# ReflowMaster.net
KiCad netlist of a schematic drawn in EAGLE
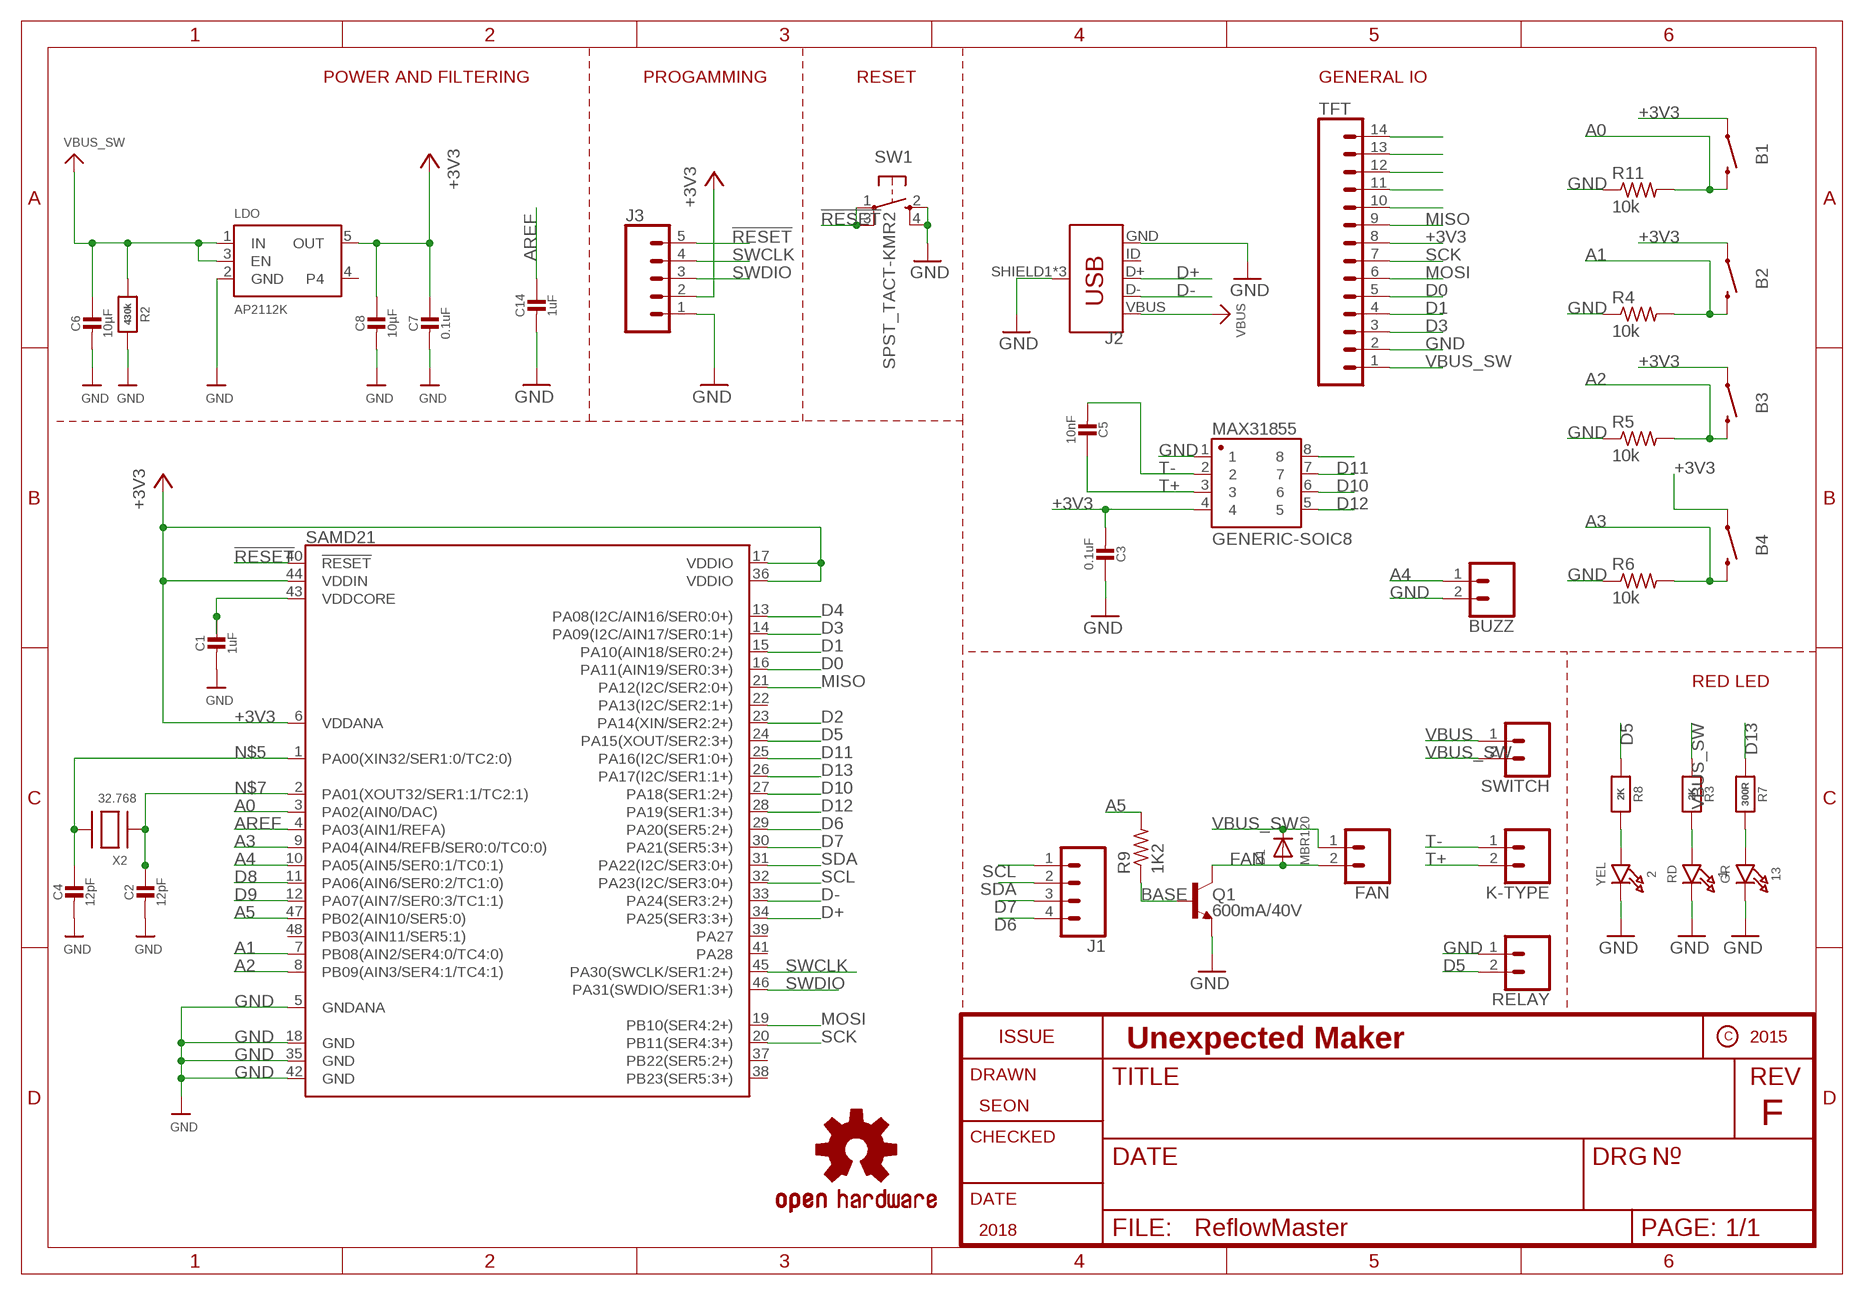
[diagram p0: schematic, sheet 1]

(export (version "E")
  (design (tool "Eeschema 10.0.6"))
  (components
    (comp (ref "1")
      (value "RD")
      (footprint "eagle-import:CHIPLED_0805_NOOUTLINE")
      (libsource (lib "eagle-import") (part "LED0805_NOOUTLINE"))
    )
    (comp (ref "2")
      (value "YEL")
      (footprint "eagle-import:CHIPLED_0805_NOOUTLINE")
      (libsource (lib "eagle-import") (part "LED0805_NOOUTLINE"))
    )
    (comp (ref "13")
      (value "GR")
      (footprint "eagle-import:CHIPLED_0805_NOOUTLINE")
      (libsource (lib "eagle-import") (part "LED0805_NOOUTLINE"))
    )
    (comp (ref "B1")
      (value "MOMENTARY-SWITCH-SPST-PTH-RIGHT-ANGLE-KIT")
      (footprint "eagle-import:TACTILE_SWITCH_PTH_RIGHT_ANGLE_KIT")
      (libsource (lib "eagle-import") (part "MOMENTARY-SWITCH-SPST-PTH-RIGHT-ANGLE-KIT"))
    )
    (comp (ref "B2")
      (value "MOMENTARY-SWITCH-SPST-PTH-RIGHT-ANGLE-KIT")
      (footprint "eagle-import:TACTILE_SWITCH_PTH_RIGHT_ANGLE_KIT")
      (libsource (lib "eagle-import") (part "MOMENTARY-SWITCH-SPST-PTH-RIGHT-ANGLE-KIT"))
    )
    (comp (ref "B3")
      (value "MOMENTARY-SWITCH-SPST-PTH-RIGHT-ANGLE-KIT")
      (footprint "eagle-import:TACTILE_SWITCH_PTH_RIGHT_ANGLE_KIT")
      (libsource (lib "eagle-import") (part "MOMENTARY-SWITCH-SPST-PTH-RIGHT-ANGLE-KIT"))
    )
    (comp (ref "B4")
      (value "MOMENTARY-SWITCH-SPST-PTH-RIGHT-ANGLE-KIT")
      (footprint "eagle-import:TACTILE_SWITCH_PTH_RIGHT_ANGLE_KIT")
      (libsource (lib "eagle-import") (part "MOMENTARY-SWITCH-SPST-PTH-RIGHT-ANGLE-KIT"))
    )
    (comp (ref "BUZZ")
      (value "CONN_02")
      (footprint "eagle-import:1X02")
      (libsource (lib "eagle-import") (part "CONN_02"))
    )
    (comp (ref "C1")
      (value "1uF")
      (footprint "eagle-import:0805-NO")
      (libsource (lib "eagle-import") (part "CAP_CERAMIC0805-NOOUTLINE"))
    )
    (comp (ref "C2")
      (value "12pF")
      (footprint "eagle-import:0805-NO")
      (libsource (lib "eagle-import") (part "CAP_CERAMIC0805-NOOUTLINE"))
    )
    (comp (ref "C3")
      (value "0.1uF")
      (footprint "eagle-import:0805-NO")
      (libsource (lib "eagle-import") (part "CAP_CERAMIC0805-NOOUTLINE"))
    )
    (comp (ref "C4")
      (value "12pF")
      (footprint "eagle-import:0805-NO")
      (libsource (lib "eagle-import") (part "CAP_CERAMIC0805-NOOUTLINE"))
    )
    (comp (ref "C5")
      (value "10nF")
      (footprint "eagle-import:0805-NO")
      (libsource (lib "eagle-import") (part "CAP_CERAMIC0805-NOOUTLINE"))
    )
    (comp (ref "C6")
      (value "10µF")
      (footprint "eagle-import:0805-NO")
      (libsource (lib "eagle-import") (part "CAP_CERAMIC0805-NOOUTLINE"))
    )
    (comp (ref "C7")
      (value "0.1uF")
      (footprint "eagle-import:0805-NO")
      (libsource (lib "eagle-import") (part "CAP_CERAMIC0805-NOOUTLINE"))
    )
    (comp (ref "C8")
      (value "10µF")
      (footprint "eagle-import:0805-NO")
      (libsource (lib "eagle-import") (part "CAP_CERAMIC0805-NOOUTLINE"))
    )
    (comp (ref "C14")
      (value "1uF")
      (footprint "eagle-import:0805-NO")
      (libsource (lib "eagle-import") (part "CAP_CERAMIC0805-NOOUTLINE"))
    )
    (comp (ref "D1")
      (value "MBR120")
      (footprint "eagle-import:SOD-123")
      (libsource (lib "eagle-import") (part "DIODESOD-123"))
    )
    (comp (ref "FAN")
      (value "CONN_02")
      (footprint "eagle-import:1X02")
      (libsource (lib "eagle-import") (part "CONN_02"))
    )
    (comp (ref "J1")
      (value "CONN_041X04_NO_SILK")
      (footprint "eagle-import:1X04_NO_SILK")
      (libsource (lib "eagle-import") (part "CONN_041X04_NO_SILK"))
    )
    (comp (ref "J2")
      (value "USB_MICRO-B_FEMALE-SMT")
      (footprint "eagle-import:USB-B-MICRO-SMD")
      (libsource (lib "eagle-import") (part "USB_MICRO-B_FEMALE-SMT"))
    )
    (comp (ref "J3")
      (value "CONN_05NO_SILK")
      (footprint "eagle-import:1X05_NO_SILK")
      (libsource (lib "eagle-import") (part "CONN_05NO_SILK"))
    )
    (comp (ref "K-TYPE")
      (value "CONN_02")
      (footprint "eagle-import:1X02")
      (libsource (lib "eagle-import") (part "CONN_02"))
    )
    (comp (ref "LDO")
      (value "AP2112K")
      (footprint "eagle-import:SOT23-5")
      (libsource (lib "eagle-import") (part "VREG_SOT23-5"))
    )
    (comp (ref "LOGO1")
      (value "OSHW-LOGOS")
      (footprint "eagle-import:OSHW-LOGO-S")
      (libsource (lib "eagle-import") (part "OSHW-LOGOS"))
    )
    (comp (ref "MAX31855")
      (value "GENERIC-SOIC8")
      (footprint "eagle-import:SO08-UNIVERSAL")
      (libsource (lib "eagle-import") (part "GENERIC-SOIC8"))
    )
    (comp (ref "Q1")
      (value "600mA/40V")
      (footprint "eagle-import:SOT23-3")
      (libsource (lib "eagle-import") (part "TRANS_NPN-MMBT2222AL"))
    )
    (comp (ref "R2")
      (value "430k")
      (footprint "eagle-import:0805-NO")
      (libsource (lib "eagle-import") (part "RESISTOR0805_NOOUTLINE"))
    )
    (comp (ref "R3")
      (value "2K")
      (footprint "eagle-import:0805-NO")
      (libsource (lib "eagle-import") (part "RESISTOR0805_NOOUTLINE"))
    )
    (comp (ref "R4")
      (value "10k")
      (footprint "eagle-import:R0805")
      (libsource (lib "eagle-import") (part "R-US_R0805"))
    )
    (comp (ref "R5")
      (value "10k")
      (footprint "eagle-import:R0805")
      (libsource (lib "eagle-import") (part "R-US_R0805"))
    )
    (comp (ref "R6")
      (value "10k")
      (footprint "eagle-import:R0805")
      (libsource (lib "eagle-import") (part "R-US_R0805"))
    )
    (comp (ref "R7")
      (value "300R")
      (footprint "eagle-import:0805-NO")
      (libsource (lib "eagle-import") (part "RESISTOR0805_NOOUTLINE"))
    )
    (comp (ref "R8")
      (value "2K")
      (footprint "eagle-import:0805-NO")
      (libsource (lib "eagle-import") (part "RESISTOR0805_NOOUTLINE"))
    )
    (comp (ref "R9")
      (value "1K2")
      (footprint "eagle-import:R0805")
      (libsource (lib "eagle-import") (part "R-US_R0805"))
    )
    (comp (ref "R11")
      (value "10k")
      (footprint "eagle-import:R0805")
      (libsource (lib "eagle-import") (part "R-US_R0805"))
    )
    (comp (ref "RELAY")
      (value "CONN_02")
      (footprint "eagle-import:1X02")
      (libsource (lib "eagle-import") (part "CONN_02"))
    )
    (comp (ref "SAMD21")
      (value "ATSAMD21G-A")
      (footprint "eagle-import:TQFP-48")
      (libsource (lib "eagle-import") (part "ATSAMD21G-A"))
    )
    (comp (ref "SW1")
      (value "SPST_TACT-KMR2")
      (footprint "eagle-import:KMR2")
      (libsource (lib "eagle-import") (part "SPST_TACT-KMR2"))
    )
    (comp (ref "SWITCH")
      (value "CONN_02")
      (footprint "eagle-import:1X02")
      (libsource (lib "eagle-import") (part "CONN_02"))
    )
    (comp (ref "TFT")
      (value "CONN_14NO_SILK")
      (footprint "eagle-import:1X14_NO_SILK")
      (libsource (lib "eagle-import") (part "CONN_14NO_SILK"))
    )
    (comp (ref "X2")
      (value "32.768")
      (footprint "eagle-import:XTAL3215")
      (libsource (lib "eagle-import") (part "XTAL-3.2X1.5"))
    )
  )
  (nets
    (net (code "1") (name "+3V3") (class "Default")
      (node (ref "B1") (pin "1") (pinfunction "1_1") (pintype "passive"))
      (node (ref "B2") (pin "1") (pinfunction "1_1") (pintype "passive"))
      (node (ref "B3") (pin "1") (pinfunction "1_1") (pintype "passive"))
      (node (ref "B4") (pin "1") (pinfunction "1_1") (pintype "passive"))
      (node (ref "C3") (pin "2") (pinfunction "2_2") (pintype "passive"))
      (node (ref "C7") (pin "1") (pinfunction "1_1") (pintype "passive"))
      (node (ref "C8") (pin "1") (pinfunction "1_1") (pintype "passive"))
      (node (ref "J3") (pin "2") (pinfunction "2_2") (pintype "passive"))
      (node (ref "LDO") (pin "5") (pinfunction "OUT_5") (pintype "power_in"))
      (node (ref "MAX31855") (pin "4") (pinfunction "4_4") (pintype "bidirectional"))
      (node (ref "SAMD21") (pin "17") (pinfunction "VDDIO_17") (pintype "bidirectional"))
      (node (ref "SAMD21") (pin "36") (pinfunction "VDDIO_36") (pintype "bidirectional"))
      (node (ref "SAMD21") (pin "44") (pinfunction "VDDIN_44") (pintype "bidirectional"))
      (node (ref "SAMD21") (pin "6") (pinfunction "VDDANA_6") (pintype "bidirectional"))
      (node (ref "TFT") (pin "8") (pinfunction "8_8") (pintype "passive"))
    )
    (net (code "2") (name "/A0") (class "Default")
      (node (ref "B1") (pin "2") (pinfunction "2_2") (pintype "passive"))
      (node (ref "R11") (pin "2") (pinfunction "2_2") (pintype "passive"))
      (node (ref "SAMD21") (pin "3") (pinfunction "PA02(AIN0/DAC)_3") (pintype "bidirectional"))
    )
    (net (code "3") (name "/A1") (class "Default")
      (node (ref "B2") (pin "2") (pinfunction "2_2") (pintype "passive"))
      (node (ref "R4") (pin "2") (pinfunction "2_2") (pintype "passive"))
      (node (ref "SAMD21") (pin "7") (pinfunction "PB08(AIN2/SER4:0/TC4:0)_7") (pintype "bidirectional"))
    )
    (net (code "4") (name "/A2") (class "Default")
      (node (ref "B3") (pin "2") (pinfunction "2_2") (pintype "passive"))
      (node (ref "R5") (pin "2") (pinfunction "2_2") (pintype "passive"))
      (node (ref "SAMD21") (pin "8") (pinfunction "PB09(AIN3/SER4:1/TC4:1)_8") (pintype "bidirectional"))
    )
    (net (code "5") (name "/A3") (class "Default")
      (node (ref "B4") (pin "2") (pinfunction "2_2") (pintype "passive"))
      (node (ref "R6") (pin "2") (pinfunction "2_2") (pintype "passive"))
      (node (ref "SAMD21") (pin "9") (pinfunction "PA04(AIN4/REFB/SER0:0/TC0:0)_9") (pintype "bidirectional"))
    )
    (net (code "6") (name "/A4") (class "Default")
      (node (ref "BUZZ") (pin "1") (pinfunction "1_1") (pintype "passive"))
      (node (ref "SAMD21") (pin "10") (pinfunction "PA05(AIN5/SER0:1/TC0:1)_10") (pintype "bidirectional"))
    )
    (net (code "7") (name "/A5") (class "Default")
      (node (ref "R9") (pin "2") (pinfunction "2_2") (pintype "passive"))
      (node (ref "SAMD21") (pin "47") (pinfunction "PB02(AIN10/SER5:0)_47") (pintype "bidirectional"))
    )
    (net (code "8") (name "/AREF") (class "Default")
      (node (ref "C14") (pin "1") (pinfunction "1_1") (pintype "passive"))
      (node (ref "SAMD21") (pin "4") (pinfunction "PA03(AIN1/REFA)_4") (pintype "bidirectional"))
    )
    (net (code "9") (name "/BASE") (class "Default")
      (node (ref "Q1") (pin "1") (pinfunction "B_1") (pintype "passive"))
      (node (ref "R9") (pin "1") (pinfunction "1_1") (pintype "passive"))
    )
    (net (code "10") (name "/D+") (class "Default")
      (node (ref "J2") (pin "D+") (pinfunction "D+_D+") (pintype "bidirectional"))
      (node (ref "SAMD21") (pin "34") (pinfunction "PA25(SER3:3+)_34") (pintype "bidirectional"))
    )
    (net (code "11") (name "/D-") (class "Default")
      (node (ref "J2") (pin "D-") (pinfunction "D-_D-") (pintype "bidirectional"))
      (node (ref "SAMD21") (pin "33") (pinfunction "PA24(SER3:2+)_33") (pintype "bidirectional"))
    )
    (net (code "12") (name "/D0") (class "Default")
      (node (ref "SAMD21") (pin "16") (pinfunction "PA11(AIN19/SER0:3+)_16") (pintype "bidirectional"))
      (node (ref "TFT") (pin "5") (pinfunction "5_5") (pintype "passive"))
    )
    (net (code "13") (name "/D1") (class "Default")
      (node (ref "SAMD21") (pin "15") (pinfunction "PA10(AIN18/SER0:2+)_15") (pintype "bidirectional"))
      (node (ref "TFT") (pin "4") (pinfunction "4_4") (pintype "passive"))
    )
    (net (code "14") (name "/D2") (class "Default")
      (node (ref "SAMD21") (pin "23") (pinfunction "PA14(XIN/SER2:2+)_23") (pintype "bidirectional"))
    )
    (net (code "15") (name "/D3") (class "Default")
      (node (ref "SAMD21") (pin "14") (pinfunction "PA09(I2C/AIN17/SER0:1+)_14") (pintype "bidirectional"))
      (node (ref "TFT") (pin "3") (pinfunction "3_3") (pintype "passive"))
    )
    (net (code "16") (name "/D4") (class "Default")
      (node (ref "SAMD21") (pin "13") (pinfunction "PA08(I2C/AIN16/SER0:0+)_13") (pintype "bidirectional"))
    )
    (net (code "17") (name "/D5") (class "Default")
      (node (ref "R8") (pin "1") (pinfunction "1_1") (pintype "passive"))
      (node (ref "RELAY") (pin "2") (pinfunction "2_2") (pintype "passive"))
      (node (ref "SAMD21") (pin "24") (pinfunction "PA15(XOUT/SER2:3+)_24") (pintype "bidirectional"))
    )
    (net (code "18") (name "/D6") (class "Default")
      (node (ref "J1") (pin "4") (pinfunction "4_4") (pintype "passive"))
      (node (ref "SAMD21") (pin "29") (pinfunction "PA20(SER5:2+)_29") (pintype "bidirectional"))
    )
    (net (code "19") (name "/D7") (class "Default")
      (node (ref "J1") (pin "3") (pinfunction "3_3") (pintype "passive"))
      (node (ref "SAMD21") (pin "30") (pinfunction "PA21(SER5:3+)_30") (pintype "bidirectional"))
    )
    (net (code "20") (name "/D8") (class "Default")
      (node (ref "SAMD21") (pin "11") (pinfunction "PA06(AIN6/SER0:2/TC1:0)_11") (pintype "bidirectional"))
    )
    (net (code "21") (name "/D9") (class "Default")
      (node (ref "SAMD21") (pin "12") (pinfunction "PA07(AIN7/SER0:3/TC1:1)_12") (pintype "bidirectional"))
    )
    (net (code "22") (name "/D10") (class "Default")
      (node (ref "MAX31855") (pin "6") (pinfunction "6_6") (pintype "bidirectional"))
      (node (ref "SAMD21") (pin "27") (pinfunction "PA18(SER1:2+)_27") (pintype "bidirectional"))
    )
    (net (code "23") (name "/D11") (class "Default")
      (node (ref "MAX31855") (pin "7") (pinfunction "7_7") (pintype "bidirectional"))
      (node (ref "SAMD21") (pin "25") (pinfunction "PA16(I2C/SER1:0+)_25") (pintype "bidirectional"))
    )
    (net (code "24") (name "/D12") (class "Default")
      (node (ref "MAX31855") (pin "5") (pinfunction "5_5") (pintype "bidirectional"))
      (node (ref "SAMD21") (pin "28") (pinfunction "PA19(SER1:3+)_28") (pintype "bidirectional"))
    )
    (net (code "25") (name "/D13") (class "Default")
      (node (ref "R7") (pin "1") (pinfunction "1_1") (pintype "passive"))
      (node (ref "SAMD21") (pin "26") (pinfunction "PA17(I2C/SER1:1+)_26") (pintype "bidirectional"))
    )
    (net (code "26") (name "/FAN") (class "Default")
      (node (ref "D1") (pin "A") (pinfunction "A_A") (pintype "passive"))
      (node (ref "FAN") (pin "2") (pinfunction "2_2") (pintype "passive"))
      (node (ref "Q1") (pin "3") (pinfunction "C_3") (pintype "passive"))
    )
    (net (code "27") (name "/MISO") (class "Default")
      (node (ref "SAMD21") (pin "21") (pinfunction "PA12(I2C/SER2:0+)_21") (pintype "bidirectional"))
      (node (ref "TFT") (pin "9") (pinfunction "9_9") (pintype "passive"))
    )
    (net (code "28") (name "/MOSI") (class "Default")
      (node (ref "SAMD21") (pin "19") (pinfunction "PB10(SER4:2+)_19") (pintype "bidirectional"))
      (node (ref "TFT") (pin "6") (pinfunction "6_6") (pintype "passive"))
    )
    (net (code "29") (name "/N$5") (class "Default")
      (node (ref "C4") (pin "1") (pinfunction "1_1") (pintype "passive"))
      (node (ref "SAMD21") (pin "1") (pinfunction "PA00(XIN32/SER1:0/TC2:0)_1") (pintype "bidirectional"))
      (node (ref "X2") (pin "P$2") (pinfunction "P$2_P$2") (pintype "bidirectional"))
    )
    (net (code "30") (name "/N$7") (class "Default")
      (node (ref "C2") (pin "1") (pinfunction "1_1") (pintype "passive"))
      (node (ref "SAMD21") (pin "2") (pinfunction "PA01(XOUT32/SER1:1/TC2:1)_2") (pintype "bidirectional"))
      (node (ref "X2") (pin "P$1") (pinfunction "P$1_P$1") (pintype "bidirectional"))
    )
    (net (code "31") (name "/SCK") (class "Default")
      (node (ref "SAMD21") (pin "20") (pinfunction "PB11(SER4:3+)_20") (pintype "bidirectional"))
      (node (ref "TFT") (pin "7") (pinfunction "7_7") (pintype "passive"))
    )
    (net (code "32") (name "/SCL") (class "Default")
      (node (ref "J1") (pin "1") (pinfunction "1_1") (pintype "passive"))
      (node (ref "SAMD21") (pin "32") (pinfunction "PA23(I2C/SER3:0+)_32") (pintype "bidirectional"))
    )
    (net (code "33") (name "/SDA") (class "Default")
      (node (ref "J1") (pin "2") (pinfunction "2_2") (pintype "passive"))
      (node (ref "SAMD21") (pin "31") (pinfunction "PA22(I2C/SER3:0+)_31") (pintype "bidirectional"))
    )
    (net (code "34") (name "/SWCLK") (class "Default")
      (node (ref "J3") (pin "4") (pinfunction "4_4") (pintype "passive"))
      (node (ref "SAMD21") (pin "45") (pinfunction "PA30(SWCLK/SER1:2+)_45") (pintype "bidirectional"))
    )
    (net (code "35") (name "/SWDIO") (class "Default")
      (node (ref "J3") (pin "3") (pinfunction "3_3") (pintype "passive"))
      (node (ref "SAMD21") (pin "46") (pinfunction "PA31(SWDIO/SER1:3+)_46") (pintype "bidirectional"))
    )
    (net (code "36") (name "/T+") (class "Default")
      (node (ref "C5") (pin "1") (pinfunction "1_1") (pintype "passive"))
      (node (ref "K-TYPE") (pin "2") (pinfunction "2_2") (pintype "passive"))
      (node (ref "MAX31855") (pin "3") (pinfunction "3_3") (pintype "bidirectional"))
    )
    (net (code "37") (name "/T-") (class "Default")
      (node (ref "C5") (pin "2") (pinfunction "2_2") (pintype "passive"))
      (node (ref "K-TYPE") (pin "1") (pinfunction "1_1") (pintype "passive"))
      (node (ref "MAX31855") (pin "2") (pinfunction "2_2") (pintype "bidirectional"))
    )
    (net (code "38") (name "/~{RESET}") (class "Default")
      (node (ref "J3") (pin "5") (pinfunction "5_5") (pintype "passive"))
      (node (ref "SAMD21") (pin "40") (pinfunction "~{RESET}_40") (pintype "bidirectional"))
      (node (ref "SW1") (pin "1") (pinfunction "P_1") (pintype "passive"))
      (node (ref "SW1") (pin "3") (pinfunction "P1_3") (pintype "passive"))
    )
    (net (code "39") (name "GND") (class "Default")
      (node (ref "1") (pin "C") (pinfunction "C_C") (pintype "passive"))
      (node (ref "13") (pin "C") (pinfunction "C_C") (pintype "passive"))
      (node (ref "2") (pin "C") (pinfunction "C_C") (pintype "passive"))
      (node (ref "BUZZ") (pin "2") (pinfunction "2_2") (pintype "passive"))
      (node (ref "C1") (pin "2") (pinfunction "2_2") (pintype "passive"))
      (node (ref "C14") (pin "2") (pinfunction "2_2") (pintype "passive"))
      (node (ref "C2") (pin "2") (pinfunction "2_2") (pintype "passive"))
      (node (ref "C3") (pin "1") (pinfunction "1_1") (pintype "passive"))
      (node (ref "C4") (pin "2") (pinfunction "2_2") (pintype "passive"))
      (node (ref "C6") (pin "2") (pinfunction "2_2") (pintype "passive"))
      (node (ref "C7") (pin "2") (pinfunction "2_2") (pintype "passive"))
      (node (ref "C8") (pin "2") (pinfunction "2_2") (pintype "passive"))
      (node (ref "J2") (pin "GND") (pinfunction "GND_GND") (pintype "power_in"))
      (node (ref "J2") (pin "SHIELD1") (pinfunction "SHIELD_SHIELD1") (pintype "bidirectional"))
      (node (ref "J2") (pin "SHIELD2") (pinfunction "SHIELD_SHIELD2") (pintype "bidirectional"))
      (node (ref "J2") (pin "SHIELD3") (pinfunction "SHIELD_SHIELD3") (pintype "bidirectional"))
      (node (ref "J3") (pin "1") (pinfunction "1_1") (pintype "passive"))
      (node (ref "LDO") (pin "2") (pinfunction "GND_2") (pintype "power_in"))
      (node (ref "MAX31855") (pin "1") (pinfunction "1_1") (pintype "bidirectional"))
      (node (ref "Q1") (pin "2") (pinfunction "E_2") (pintype "passive"))
      (node (ref "R11") (pin "1") (pinfunction "1_1") (pintype "passive"))
      (node (ref "R2") (pin "2") (pinfunction "2_2") (pintype "passive"))
      (node (ref "R4") (pin "1") (pinfunction "1_1") (pintype "passive"))
      (node (ref "R5") (pin "1") (pinfunction "1_1") (pintype "passive"))
      (node (ref "R6") (pin "1") (pinfunction "1_1") (pintype "passive"))
      (node (ref "RELAY") (pin "1") (pinfunction "1_1") (pintype "passive"))
      (node (ref "SAMD21") (pin "18") (pinfunction "GND_18") (pintype "bidirectional"))
      (node (ref "SAMD21") (pin "35") (pinfunction "GND_35") (pintype "bidirectional"))
      (node (ref "SAMD21") (pin "42") (pinfunction "GND_42") (pintype "bidirectional"))
      (node (ref "SAMD21") (pin "5") (pinfunction "GNDANA_5") (pintype "bidirectional"))
      (node (ref "SW1") (pin "2") (pinfunction "S_2") (pintype "passive"))
      (node (ref "SW1") (pin "4") (pinfunction "S1_4") (pintype "passive"))
      (node (ref "TFT") (pin "2") (pinfunction "2_2") (pintype "passive"))
    )
    (net (code "40") (name "Net-(1-PadA)") (class "Default")
      (node (ref "1") (pin "A") (pinfunction "A_A") (pintype "passive"))
      (node (ref "R3") (pin "2") (pinfunction "2_2") (pintype "passive"))
    )
    (net (code "41") (name "Net-(2-PadA)") (class "Default")
      (node (ref "2") (pin "A") (pinfunction "A_A") (pintype "passive"))
      (node (ref "R8") (pin "2") (pinfunction "2_2") (pintype "passive"))
    )
    (net (code "42") (name "Net-(13-PadA)") (class "Default")
      (node (ref "13") (pin "A") (pinfunction "A_A") (pintype "passive"))
      (node (ref "R7") (pin "2") (pinfunction "2_2") (pintype "passive"))
    )
    (net (code "43") (name "Net-(SAMD21-VDDCORE)") (class "Default")
      (node (ref "C1") (pin "1") (pinfunction "1_1") (pintype "passive"))
      (node (ref "SAMD21") (pin "43") (pinfunction "VDDCORE_43") (pintype "bidirectional"))
    )
    (net (code "44") (name "VBUS") (class "Default")
      (node (ref "J2") (pin "VBUS") (pinfunction "VBUS_VBUS") (pintype "power_in"))
      (node (ref "SWITCH") (pin "1") (pinfunction "1_1") (pintype "passive"))
    )
    (net (code "45") (name "VBUS_SW") (class "Default")
      (node (ref "C6") (pin "1") (pinfunction "1_1") (pintype "passive"))
      (node (ref "D1") (pin "C") (pinfunction "C_C") (pintype "passive"))
      (node (ref "FAN") (pin "1") (pinfunction "1_1") (pintype "passive"))
      (node (ref "LDO") (pin "1") (pinfunction "IN_1") (pintype "power_in"))
      (node (ref "LDO") (pin "3") (pinfunction "EN_3") (pintype "input"))
      (node (ref "R2") (pin "1") (pinfunction "1_1") (pintype "passive"))
      (node (ref "R3") (pin "1") (pinfunction "1_1") (pintype "passive"))
      (node (ref "SWITCH") (pin "2") (pinfunction "2_2") (pintype "passive"))
      (node (ref "TFT") (pin "1") (pinfunction "1_1") (pintype "passive"))
    )
    (net (code "46") (name "unconnected-(J2-PadID)") (class "Default")
      (node (ref "J2") (pin "ID") (pinfunction "ID_ID") (pintype "bidirectional"))
    )
    (net (code "47") (name "unconnected-(LDO-P4-Pad4)") (class "Default")
      (node (ref "LDO") (pin "4") (pinfunction "P4_4") (pintype "bidirectional"))
    )
    (net (code "48") (name "unconnected-(MAX31855-Pad8)") (class "Default")
      (node (ref "MAX31855") (pin "8") (pinfunction "8_8") (pintype "bidirectional"))
    )
    (net (code "49") (name "unconnected-(SAMD21-PA13(I2C{slash}SER2:1+)-Pad22)") (class "Default")
      (node (ref "SAMD21") (pin "22") (pinfunction "PA13(I2C/SER2:1+)_22") (pintype "bidirectional"))
    )
    (net (code "50") (name "unconnected-(SAMD21-PA27-Pad39)") (class "Default")
      (node (ref "SAMD21") (pin "39") (pinfunction "PA27_39") (pintype "bidirectional"))
    )
    (net (code "51") (name "unconnected-(SAMD21-PA28-Pad41)") (class "Default")
      (node (ref "SAMD21") (pin "41") (pinfunction "PA28_41") (pintype "bidirectional"))
    )
    (net (code "52") (name "unconnected-(SAMD21-PB03(AIN11{slash}SER5:1)-Pad48)") (class "Default")
      (node (ref "SAMD21") (pin "48") (pinfunction "PB03(AIN11/SER5:1)_48") (pintype "bidirectional"))
    )
    (net (code "53") (name "unconnected-(SAMD21-PB22(SER5:2+)-Pad37)") (class "Default")
      (node (ref "SAMD21") (pin "37") (pinfunction "PB22(SER5:2+)_37") (pintype "bidirectional"))
    )
    (net (code "54") (name "unconnected-(SAMD21-PB23(SER5:3+)-Pad38)") (class "Default")
      (node (ref "SAMD21") (pin "38") (pinfunction "PB23(SER5:3+)_38") (pintype "bidirectional"))
    )
    (net (code "55") (name "unconnected-(TFT-Pad10)") (class "Default")
      (node (ref "TFT") (pin "10") (pinfunction "10_10") (pintype "passive"))
    )
    (net (code "56") (name "unconnected-(TFT-Pad11)") (class "Default")
      (node (ref "TFT") (pin "11") (pinfunction "11_11") (pintype "passive"))
    )
    (net (code "57") (name "unconnected-(TFT-Pad12)") (class "Default")
      (node (ref "TFT") (pin "12") (pinfunction "12_12") (pintype "passive"))
    )
    (net (code "58") (name "unconnected-(TFT-Pad13)") (class "Default")
      (node (ref "TFT") (pin "13") (pinfunction "13_13") (pintype "passive"))
    )
    (net (code "59") (name "unconnected-(TFT-Pad14)") (class "Default")
      (node (ref "TFT") (pin "14") (pinfunction "14_14") (pintype "passive"))
    )
  )
)
